# QFN16.net
KiCad netlist of a schematic drawn in EAGLE
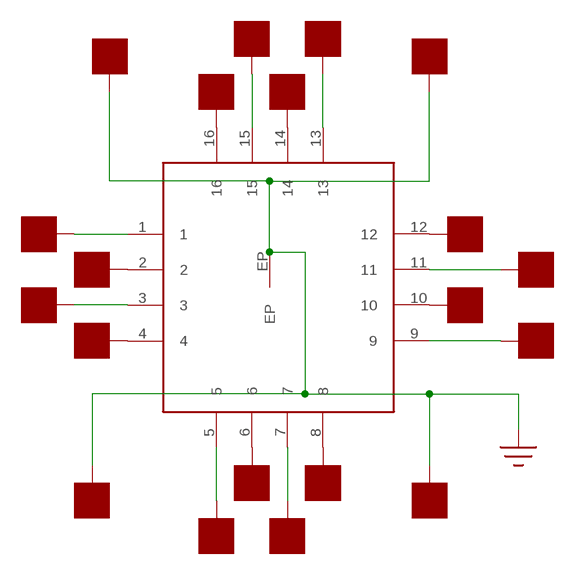
[diagram p0: schematic, sheet 1]

(export (version "E")
  (design (tool "Eeschema 10.0.6"))
  (components
    (comp (ref "U$1")
      (value "QFN16")
      (footprint "eagle-import:TQFN16-EP")
      (libsource (lib "eagle-import") (part "QFN16"))
    )
    (comp (ref "U$2")
      (value "PAD50MIL")
      (footprint "eagle-import:PAD_50MIL")
      (libsource (lib "eagle-import") (part "PAD50MIL"))
    )
    (comp (ref "U$3")
      (value "PAD50MIL")
      (footprint "eagle-import:PAD_50MIL")
      (libsource (lib "eagle-import") (part "PAD50MIL"))
    )
    (comp (ref "U$4")
      (value "PAD50MIL")
      (footprint "eagle-import:PAD_50MIL")
      (libsource (lib "eagle-import") (part "PAD50MIL"))
    )
    (comp (ref "U$5")
      (value "PAD50MIL")
      (footprint "eagle-import:PAD_50MIL")
      (libsource (lib "eagle-import") (part "PAD50MIL"))
    )
    (comp (ref "U$6")
      (value "PAD50MIL")
      (footprint "eagle-import:PAD_50MIL")
      (libsource (lib "eagle-import") (part "PAD50MIL"))
    )
    (comp (ref "U$7")
      (value "PAD50MIL")
      (footprint "eagle-import:PAD_50MIL")
      (libsource (lib "eagle-import") (part "PAD50MIL"))
    )
    (comp (ref "U$8")
      (value "PAD50MIL")
      (footprint "eagle-import:PAD_50MIL")
      (libsource (lib "eagle-import") (part "PAD50MIL"))
    )
    (comp (ref "U$9")
      (value "PAD50MIL")
      (footprint "eagle-import:PAD_50MIL")
      (libsource (lib "eagle-import") (part "PAD50MIL"))
    )
    (comp (ref "U$10")
      (value "PAD50MIL")
      (footprint "eagle-import:PAD_50MIL")
      (libsource (lib "eagle-import") (part "PAD50MIL"))
    )
    (comp (ref "U$11")
      (value "PAD50MIL")
      (footprint "eagle-import:PAD_50MIL")
      (libsource (lib "eagle-import") (part "PAD50MIL"))
    )
    (comp (ref "U$12")
      (value "PAD50MIL")
      (footprint "eagle-import:PAD_50MIL")
      (libsource (lib "eagle-import") (part "PAD50MIL"))
    )
    (comp (ref "U$13")
      (value "PAD50MIL")
      (footprint "eagle-import:PAD_50MIL")
      (libsource (lib "eagle-import") (part "PAD50MIL"))
    )
    (comp (ref "U$14")
      (value "PAD50MIL")
      (footprint "eagle-import:PAD_50MIL")
      (libsource (lib "eagle-import") (part "PAD50MIL"))
    )
    (comp (ref "U$15")
      (value "PAD50MIL")
      (footprint "eagle-import:PAD_50MIL")
      (libsource (lib "eagle-import") (part "PAD50MIL"))
    )
    (comp (ref "U$16")
      (value "PAD50MIL")
      (footprint "eagle-import:PAD_50MIL")
      (libsource (lib "eagle-import") (part "PAD50MIL"))
    )
    (comp (ref "U$17")
      (value "PAD50MIL")
      (footprint "eagle-import:PAD_50MIL")
      (libsource (lib "eagle-import") (part "PAD50MIL"))
    )
    (comp (ref "U$18")
      (value "PAD50MIL")
      (footprint "eagle-import:PAD_50MIL")
      (libsource (lib "eagle-import") (part "PAD50MIL"))
    )
    (comp (ref "U$19")
      (value "PAD50MIL")
      (footprint "eagle-import:PAD_50MIL")
      (libsource (lib "eagle-import") (part "PAD50MIL"))
    )
    (comp (ref "U$20")
      (value "PAD50MIL")
      (footprint "eagle-import:PAD_50MIL")
      (libsource (lib "eagle-import") (part "PAD50MIL"))
    )
    (comp (ref "U$21")
      (value "PAD50MIL")
      (footprint "eagle-import:PAD_50MIL")
      (libsource (lib "eagle-import") (part "PAD50MIL"))
    )
  )
  (nets
    (net (code "1") (name "GND") (class "Default")
      (node (ref "U$1") (pin "EP") (pinfunction "EP_EP") (pintype "bidirectional"))
      (node (ref "U$18") (pin "P$1") (pinfunction "P$1_P$1") (pintype "bidirectional"))
      (node (ref "U$19") (pin "P$1") (pinfunction "P$1_P$1") (pintype "bidirectional"))
      (node (ref "U$20") (pin "P$1") (pinfunction "P$1_P$1") (pintype "bidirectional"))
      (node (ref "U$21") (pin "P$1") (pinfunction "P$1_P$1") (pintype "bidirectional"))
    )
    (net (code "2") (name "Net-(U$1-Pad1)") (class "Default")
      (node (ref "U$1") (pin "1") (pinfunction "1_1") (pintype "bidirectional"))
      (node (ref "U$13") (pin "P$1") (pinfunction "P$1_P$1") (pintype "bidirectional"))
    )
    (net (code "3") (name "Net-(U$1-Pad2)") (class "Default")
      (node (ref "U$1") (pin "2") (pinfunction "2_2") (pintype "bidirectional"))
      (node (ref "U$12") (pin "P$1") (pinfunction "P$1_P$1") (pintype "bidirectional"))
    )
    (net (code "4") (name "Net-(U$1-Pad3)") (class "Default")
      (node (ref "U$1") (pin "3") (pinfunction "3_3") (pintype "bidirectional"))
      (node (ref "U$11") (pin "P$1") (pinfunction "P$1_P$1") (pintype "bidirectional"))
    )
    (net (code "5") (name "Net-(U$1-Pad4)") (class "Default")
      (node (ref "U$1") (pin "4") (pinfunction "4_4") (pintype "bidirectional"))
      (node (ref "U$10") (pin "P$1") (pinfunction "P$1_P$1") (pintype "bidirectional"))
    )
    (net (code "6") (name "Net-(U$1-Pad5)") (class "Default")
      (node (ref "U$1") (pin "5") (pinfunction "5_5") (pintype "bidirectional"))
      (node (ref "U$9") (pin "P$1") (pinfunction "P$1_P$1") (pintype "bidirectional"))
    )
    (net (code "7") (name "Net-(U$1-Pad6)") (class "Default")
      (node (ref "U$1") (pin "6") (pinfunction "6_6") (pintype "bidirectional"))
      (node (ref "U$8") (pin "P$1") (pinfunction "P$1_P$1") (pintype "bidirectional"))
    )
    (net (code "8") (name "Net-(U$1-Pad7)") (class "Default")
      (node (ref "U$1") (pin "7") (pinfunction "7_7") (pintype "bidirectional"))
      (node (ref "U$7") (pin "P$1") (pinfunction "P$1_P$1") (pintype "bidirectional"))
    )
    (net (code "9") (name "Net-(U$1-Pad8)") (class "Default")
      (node (ref "U$1") (pin "8") (pinfunction "8_8") (pintype "bidirectional"))
      (node (ref "U$6") (pin "P$1") (pinfunction "P$1_P$1") (pintype "bidirectional"))
    )
    (net (code "10") (name "Net-(U$1-Pad9)") (class "Default")
      (node (ref "U$1") (pin "9") (pinfunction "9_9") (pintype "bidirectional"))
      (node (ref "U$5") (pin "P$1") (pinfunction "P$1_P$1") (pintype "bidirectional"))
    )
    (net (code "11") (name "Net-(U$1-Pad10)") (class "Default")
      (node (ref "U$1") (pin "10") (pinfunction "10_10") (pintype "bidirectional"))
      (node (ref "U$4") (pin "P$1") (pinfunction "P$1_P$1") (pintype "bidirectional"))
    )
    (net (code "12") (name "Net-(U$1-Pad11)") (class "Default")
      (node (ref "U$1") (pin "11") (pinfunction "11_11") (pintype "bidirectional"))
      (node (ref "U$3") (pin "P$1") (pinfunction "P$1_P$1") (pintype "bidirectional"))
    )
    (net (code "13") (name "Net-(U$1-Pad12)") (class "Default")
      (node (ref "U$1") (pin "12") (pinfunction "12_12") (pintype "bidirectional"))
      (node (ref "U$2") (pin "P$1") (pinfunction "P$1_P$1") (pintype "bidirectional"))
    )
    (net (code "14") (name "Net-(U$1-Pad13)") (class "Default")
      (node (ref "U$1") (pin "13") (pinfunction "13_13") (pintype "bidirectional"))
      (node (ref "U$17") (pin "P$1") (pinfunction "P$1_P$1") (pintype "bidirectional"))
    )
    (net (code "15") (name "Net-(U$1-Pad14)") (class "Default")
      (node (ref "U$1") (pin "14") (pinfunction "14_14") (pintype "bidirectional"))
      (node (ref "U$16") (pin "P$1") (pinfunction "P$1_P$1") (pintype "bidirectional"))
    )
    (net (code "16") (name "Net-(U$1-Pad15)") (class "Default")
      (node (ref "U$1") (pin "15") (pinfunction "15_15") (pintype "bidirectional"))
      (node (ref "U$15") (pin "P$1") (pinfunction "P$1_P$1") (pintype "bidirectional"))
    )
    (net (code "17") (name "Net-(U$1-Pad16)") (class "Default")
      (node (ref "U$1") (pin "16") (pinfunction "16_16") (pintype "bidirectional"))
      (node (ref "U$14") (pin "P$1") (pinfunction "P$1_P$1") (pintype "bidirectional"))
    )
  )
)
